# PX4FLOW2_1_CAM_X0.net
KiCad netlist of a schematic drawn in Altium Designer
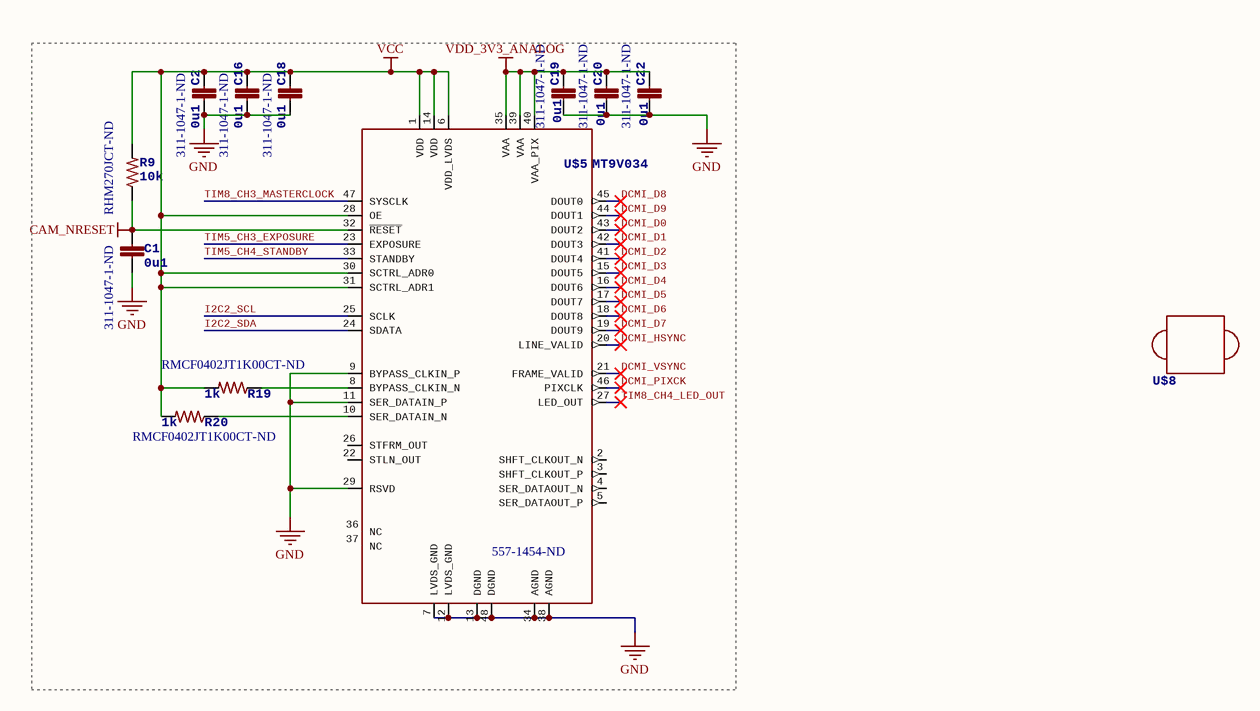
[diagram p0: PX4FLOW2.1_CAM_X0.SchDoc]

(export (version "E")
  (design (tool "Eeschema 10.0.6"))
  (components
    (comp (ref "C1")
      (value "0u1")
      (footprint "C0402")
      (description "CapacitorStandard 0603 ceramic capacitor, and 0.1\" leaded capacitor.")
      (fields
        (field (name "PARTNO") "CC0402ZRY5V7BB104")
        (field (name "SUPPLIER PART NUMBER 1") "311-1047-1-ND")
      )
      (libsource (lib "pixhawk2") (part "CAP0402-CAP"))
    )
    (comp (ref "C2")
      (value "0u1")
      (footprint "C0402")
      (description "CapacitorStandard 0603 ceramic capacitor, and 0.1\" leaded capacitor.")
      (fields
        (field (name "PARTNO") "CC0402ZRY5V7BB104")
        (field (name "SUPPLIER PART NUMBER 1") "311-1047-1-ND")
      )
      (libsource (lib "pixhawk2") (part "CAP0402-CAP"))
    )
    (comp (ref "C16")
      (value "0u1")
      (footprint "C0402")
      (description "CapacitorStandard 0603 ceramic capacitor, and 0.1\" leaded capacitor.")
      (fields
        (field (name "PARTNO") "CC0402ZRY5V7BB104")
        (field (name "SUPPLIER PART NUMBER 1") "311-1047-1-ND")
      )
      (libsource (lib "pixhawk2") (part "CAP0402-CAP"))
    )
    (comp (ref "C18")
      (value "0u1")
      (footprint "C0402")
      (description "CapacitorStandard 0603 ceramic capacitor, and 0.1\" leaded capacitor.")
      (fields
        (field (name "PARTNO") "CC0402ZRY5V7BB104")
        (field (name "SUPPLIER PART NUMBER 1") "311-1047-1-ND")
      )
      (libsource (lib "pixhawk2") (part "CAP0402-CAP"))
    )
    (comp (ref "C19")
      (value "0u1")
      (footprint "C0402")
      (description "CapacitorStandard 0603 ceramic capacitor, and 0.1\" leaded capacitor.")
      (fields
        (field (name "PARTNO") "CC0402ZRY5V7BB104")
        (field (name "SUPPLIER PART NUMBER 1") "311-1047-1-ND")
      )
      (libsource (lib "pixhawk2") (part "CAP0402-CAP"))
    )
    (comp (ref "C20")
      (value "0u1")
      (footprint "C0402")
      (description "CapacitorStandard 0603 ceramic capacitor, and 0.1\" leaded capacitor.")
      (fields
        (field (name "PARTNO") "CC0402ZRY5V7BB104")
        (field (name "SUPPLIER PART NUMBER 1") "311-1047-1-ND")
      )
      (libsource (lib "pixhawk2") (part "CAP0402-CAP"))
    )
    (comp (ref "C22")
      (value "0u1")
      (footprint "C0402")
      (description "CapacitorStandard 0603 ceramic capacitor, and 0.1\" leaded capacitor.")
      (fields
        (field (name "PARTNO") "CC0402ZRY5V7BB104")
        (field (name "SUPPLIER PART NUMBER 1") "311-1047-1-ND")
      )
      (libsource (lib "pixhawk2") (part "CAP0402-CAP"))
    )
    (comp (ref "R9")
      (value "10k")
      (footprint "R0402")
      (fields (field (name "PARTNO") "MCR01MZPJ271") (field (name "SUPPLIER PART NUMBER 1") "RHM270JCT-ND"))
      (libsource (lib "pixhawk2") (part "RESISTOR0402-RES"))
    )
    (comp (ref "R19")
      (value "1k")
      (footprint "R0402")
      (fields
        (field (name "PARTNO") "RMCF0402JT1K00")
        (field (name "SUPPLIER PART NUMBER 1") "RMCF0402JT1K00CT-ND")
      )
      (libsource (lib "pixhawk2") (part "RESISTOR0402-RES"))
    )
    (comp (ref "R20")
      (value "1k")
      (footprint "R0402")
      (fields
        (field (name "PARTNO") "RMCF0402JT1K00")
        (field (name "SUPPLIER PART NUMBER 1") "RMCF0402JT1K00CT-ND")
      )
      (libsource (lib "pixhawk2") (part "RESISTOR0402-RES"))
    )
    (comp (ref "U$5")
      (value "MT9V034")
      (footprint "CLCC-48")
      (fields (field (name "PARTNO") "MT9V034C12STM") (field (name "SUPPLIER PART NUMBER 1") "557-1454-ND"))
      (libsource (lib "3DR") (part "MT9V034"))
    )
    (comp (ref "U$8")
      (value "LENSMOUNT_M12")
      (footprint "LENSMOUNT_LARGE_M12")
      (description "Point Grey compatible M12 lens mount")
      (libsource (lib "3DR") (part "LENSMOUNT_M12"))
    )
  )
  (nets
    (net (code "1") (name "/DCMI_D0") (class "Default")
      (node (ref "U$5") (pin "43") (pinfunction "DOUT2_43") (pintype "output+no_connect"))
    )
    (net (code "2") (name "/DCMI_D1") (class "Default")
      (node (ref "U$5") (pin "42") (pinfunction "DOUT3_42") (pintype "output+no_connect"))
    )
    (net (code "3") (name "/DCMI_D2") (class "Default")
      (node (ref "U$5") (pin "41") (pinfunction "DOUT4_41") (pintype "output+no_connect"))
    )
    (net (code "4") (name "/DCMI_D3") (class "Default")
      (node (ref "U$5") (pin "15") (pinfunction "DOUT5_15") (pintype "output+no_connect"))
    )
    (net (code "5") (name "/DCMI_D4") (class "Default")
      (node (ref "U$5") (pin "16") (pinfunction "DOUT6_16") (pintype "output+no_connect"))
    )
    (net (code "6") (name "/DCMI_D5") (class "Default")
      (node (ref "U$5") (pin "17") (pinfunction "DOUT7_17") (pintype "output+no_connect"))
    )
    (net (code "7") (name "/DCMI_D6") (class "Default")
      (node (ref "U$5") (pin "18") (pinfunction "DOUT8_18") (pintype "output+no_connect"))
    )
    (net (code "8") (name "/DCMI_D7") (class "Default")
      (node (ref "U$5") (pin "19") (pinfunction "DOUT9_19") (pintype "output+no_connect"))
    )
    (net (code "9") (name "/DCMI_D8") (class "Default")
      (node (ref "U$5") (pin "45") (pinfunction "DOUT0_45") (pintype "output+no_connect"))
    )
    (net (code "10") (name "/DCMI_D9") (class "Default")
      (node (ref "U$5") (pin "44") (pinfunction "DOUT1_44") (pintype "output+no_connect"))
    )
    (net (code "11") (name "/DCMI_HSYNC") (class "Default")
      (node (ref "U$5") (pin "20") (pinfunction "LINE_VALID_20") (pintype "output+no_connect"))
    )
    (net (code "12") (name "/DCMI_PIXCK") (class "Default")
      (node (ref "U$5") (pin "46") (pinfunction "PIXCLK_46") (pintype "output+no_connect"))
    )
    (net (code "13") (name "/DCMI_VSYNC") (class "Default")
      (node (ref "U$5") (pin "21") (pinfunction "FRAME_VALID_21") (pintype "output+no_connect"))
    )
    (net (code "14") (name "/I2C2_SCL") (class "Default")
      (node (ref "U$5") (pin "25") (pinfunction "SCLK_25") (pintype "passive"))
    )
    (net (code "15") (name "/I2C2_SDA") (class "Default")
      (node (ref "U$5") (pin "24") (pinfunction "SDATA_24") (pintype "passive"))
    )
    (net (code "16") (name "/TIM5_CH3_EXPOSURE") (class "Default")
      (node (ref "U$5") (pin "23") (pinfunction "EXPOSURE_23") (pintype "passive"))
    )
    (net (code "17") (name "/TIM5_CH4_STANDBY") (class "Default")
      (node (ref "U$5") (pin "33") (pinfunction "STANDBY_33") (pintype "passive"))
    )
    (net (code "18") (name "/TIM8_CH3_MASTERCLOCK") (class "Default")
      (node (ref "U$5") (pin "47") (pinfunction "SYSCLK_47") (pintype "passive"))
    )
    (net (code "19") (name "/TIM8_CH4_LED_OUT") (class "Default")
      (node (ref "U$5") (pin "27") (pinfunction "LED_OUT_27") (pintype "output+no_connect"))
    )
    (net (code "20") (name "CAM_NRESET") (class "Default")
      (node (ref "C1") (pin "1") (pinfunction "1_1") (pintype "passive"))
      (node (ref "R9") (pin "1") (pinfunction "1_1") (pintype "passive"))
      (node (ref "U$5") (pin "32") (pinfunction "~{RESET}_32") (pintype "passive"))
    )
    (net (code "21") (name "GND") (class "Default")
      (node (ref "C1") (pin "2") (pinfunction "2_2") (pintype "passive"))
      (node (ref "C16") (pin "2") (pinfunction "2_2") (pintype "passive"))
      (node (ref "C18") (pin "2") (pinfunction "2_2") (pintype "passive"))
      (node (ref "C19") (pin "2") (pinfunction "2_2") (pintype "passive"))
      (node (ref "C2") (pin "2") (pinfunction "2_2") (pintype "passive"))
      (node (ref "C20") (pin "2") (pinfunction "2_2") (pintype "passive"))
      (node (ref "C22") (pin "2") (pinfunction "2_2") (pintype "passive"))
      (node (ref "U$5") (pin "11") (pinfunction "SER_DATAIN_P_11") (pintype "passive"))
      (node (ref "U$5") (pin "12") (pinfunction "LVDS_GND_12") (pintype "power_in"))
      (node (ref "U$5") (pin "13") (pinfunction "DGND_13") (pintype "power_in"))
      (node (ref "U$5") (pin "29") (pinfunction "RSVD_29") (pintype "passive"))
      (node (ref "U$5") (pin "34") (pinfunction "AGND_34") (pintype "power_in"))
      (node (ref "U$5") (pin "38") (pinfunction "AGND_38") (pintype "power_in"))
      (node (ref "U$5") (pin "48") (pinfunction "DGND_48") (pintype "power_in"))
      (node (ref "U$5") (pin "7") (pinfunction "LVDS_GND_7") (pintype "power_in"))
      (node (ref "U$5") (pin "9") (pinfunction "BYPASS_CLKIN_P_9") (pintype "passive"))
    )
    (net (code "22") (name "Net-(U$5-BYPASS_CLKIN_N)") (class "Default")
      (node (ref "R19") (pin "1") (pinfunction "1_1") (pintype "passive"))
      (node (ref "U$5") (pin "8") (pinfunction "BYPASS_CLKIN_N_8") (pintype "passive"))
    )
    (net (code "23") (name "Net-(U$5-SER_DATAIN_N)") (class "Default")
      (node (ref "R20") (pin "1") (pinfunction "1_1") (pintype "passive"))
      (node (ref "U$5") (pin "10") (pinfunction "SER_DATAIN_N_10") (pintype "passive"))
    )
    (net (code "24") (name "VCC") (class "Default")
      (node (ref "C16") (pin "1") (pinfunction "1_1") (pintype "passive"))
      (node (ref "C18") (pin "1") (pinfunction "1_1") (pintype "passive"))
      (node (ref "C2") (pin "1") (pinfunction "1_1") (pintype "passive"))
      (node (ref "R19") (pin "2") (pinfunction "2_2") (pintype "passive"))
      (node (ref "R20") (pin "2") (pinfunction "2_2") (pintype "passive"))
      (node (ref "R9") (pin "2") (pinfunction "2_2") (pintype "passive"))
      (node (ref "U$5") (pin "1") (pinfunction "VDD_1") (pintype "passive"))
      (node (ref "U$5") (pin "14") (pinfunction "VDD_14") (pintype "passive"))
      (node (ref "U$5") (pin "28") (pinfunction "OE_28") (pintype "passive"))
      (node (ref "U$5") (pin "30") (pinfunction "SCTRL_ADR0_30") (pintype "passive"))
      (node (ref "U$5") (pin "31") (pinfunction "SCTRL_ADR1_31") (pintype "passive"))
      (node (ref "U$5") (pin "6") (pinfunction "VDD_LVDS_6") (pintype "passive"))
    )
    (net (code "25") (name "VDD_3V3_ANALOG") (class "Default")
      (node (ref "C19") (pin "1") (pinfunction "1_1") (pintype "passive"))
      (node (ref "C20") (pin "1") (pinfunction "1_1") (pintype "passive"))
      (node (ref "C22") (pin "1") (pinfunction "1_1") (pintype "passive"))
      (node (ref "U$5") (pin "35") (pinfunction "VAA_35") (pintype "passive"))
      (node (ref "U$5") (pin "39") (pinfunction "VAA_39") (pintype "passive"))
      (node (ref "U$5") (pin "40") (pinfunction "VAA_PIX_40") (pintype "passive"))
    )
    (net (code "26") (name "unconnected-(U$5-NC-Pad36)") (class "Default")
      (node (ref "U$5") (pin "36") (pinfunction "NC_36") (pintype "passive"))
    )
    (net (code "27") (name "unconnected-(U$5-NC-Pad37)") (class "Default")
      (node (ref "U$5") (pin "37") (pinfunction "NC_37") (pintype "passive"))
    )
    (net (code "28") (name "unconnected-(U$5-SER_DATAOUT_N-Pad4)") (class "Default")
      (node (ref "U$5") (pin "4") (pinfunction "SER_DATAOUT_N_4") (pintype "output"))
    )
    (net (code "29") (name "unconnected-(U$5-SER_DATAOUT_P-Pad5)") (class "Default")
      (node (ref "U$5") (pin "5") (pinfunction "SER_DATAOUT_P_5") (pintype "output"))
    )
    (net (code "30") (name "unconnected-(U$5-SHFT_CLKOUT_N-Pad2)") (class "Default")
      (node (ref "U$5") (pin "2") (pinfunction "SHFT_CLKOUT_N_2") (pintype "output"))
    )
    (net (code "31") (name "unconnected-(U$5-SHFT_CLKOUT_P-Pad3)") (class "Default")
      (node (ref "U$5") (pin "3") (pinfunction "SHFT_CLKOUT_P_3") (pintype "output"))
    )
    (net (code "32") (name "unconnected-(U$5-STFRM_OUT-Pad26)") (class "Default")
      (node (ref "U$5") (pin "26") (pinfunction "STFRM_OUT_26") (pintype "passive"))
    )
    (net (code "33") (name "unconnected-(U$5-STLN_OUT-Pad22)") (class "Default")
      (node (ref "U$5") (pin "22") (pinfunction "STLN_OUT_22") (pintype "passive"))
    )
  )
)
